# INV_H.net
KiCad netlist of a schematic drawn in EAGLE
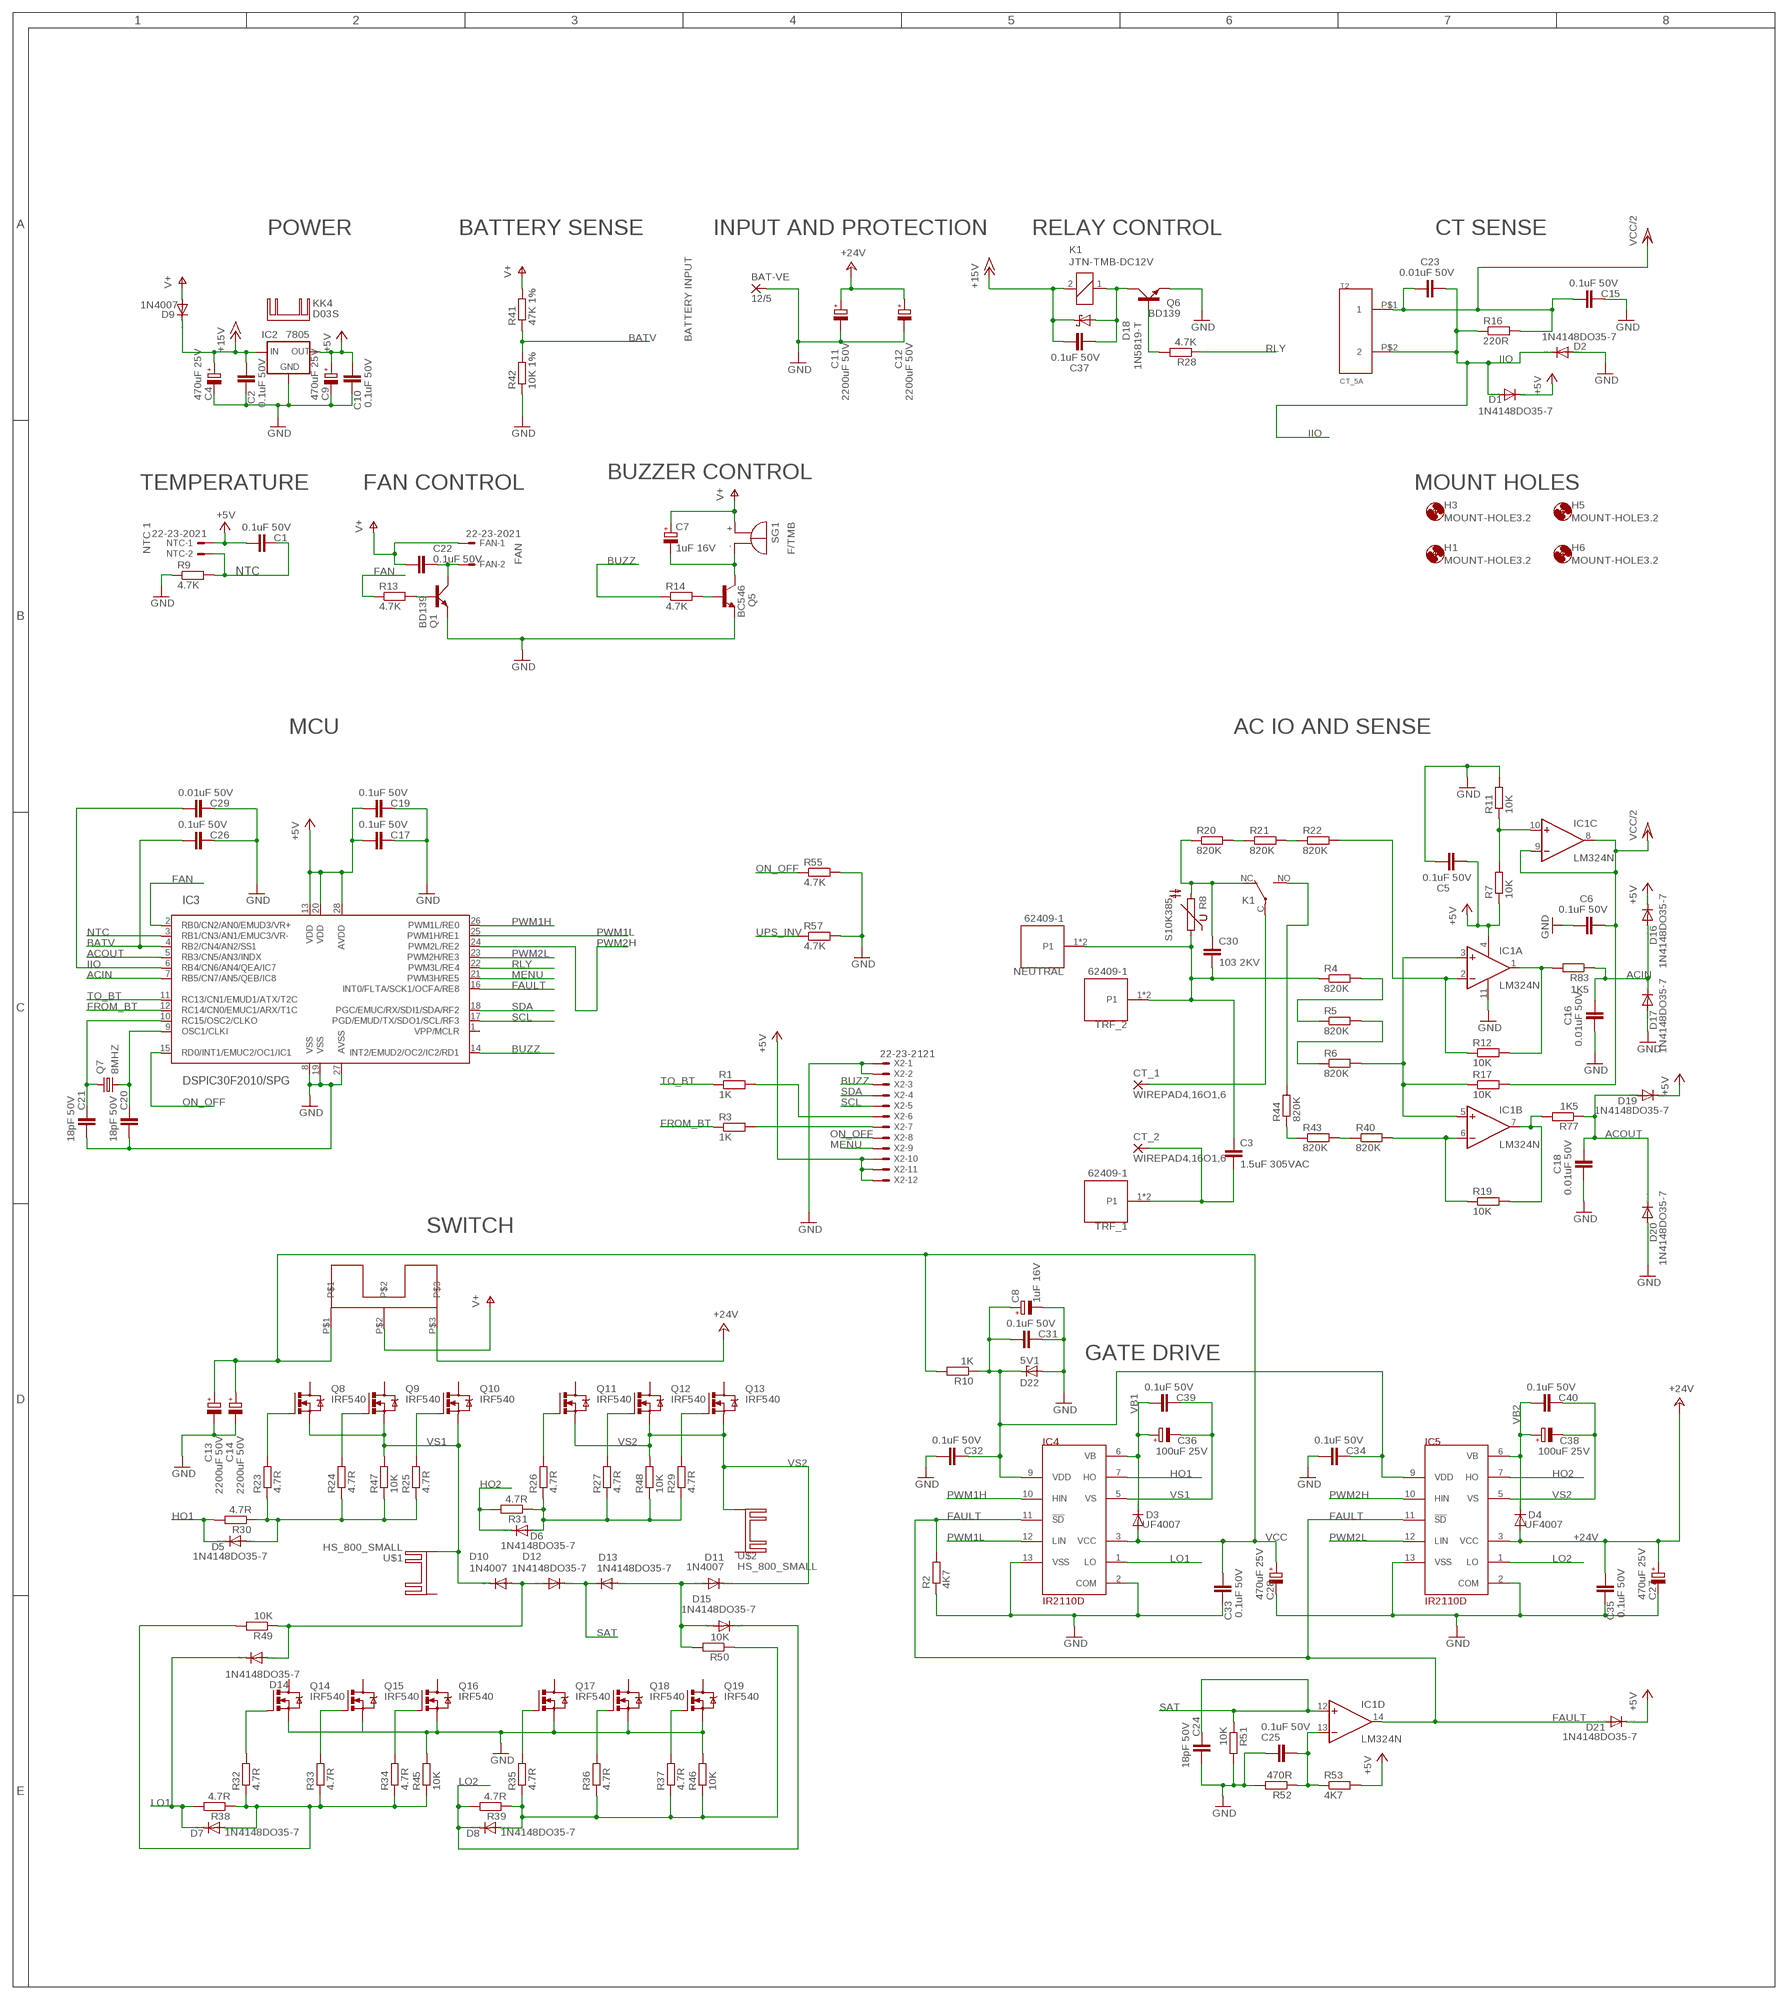
[diagram p0: schematic, sheet 1]

(export (version "E")
  (design (tool "Eeschema 10.0.6"))
  (components
    (comp (ref "BAT-VE")
      (value "12/5")
      (footprint "eagle-import:8_5")
      (libsource (lib "eagle-import") (part "12/5"))
    )
    (comp (ref "C1")
      (value "0.1uF 50V")
      (footprint "eagle-import:C025-025X050")
      (libsource (lib "eagle-import") (part "C-EU025-025X050"))
    )
    (comp (ref "C2")
      (value "0.1uF 50V")
      (footprint "eagle-import:C025-025X050")
      (libsource (lib "eagle-import") (part "C-EU025-025X050"))
    )
    (comp (ref "C3")
      (value "1.5uF 305VAC")
      (footprint "eagle-import:C275-113X316")
      (libsource (lib "eagle-import") (part "C-EU275-113X316"))
    )
    (comp (ref "C4")
      (value "470uF 25V")
      (footprint "eagle-import:E3,5-8")
      (libsource (lib "eagle-import") (part "CPOL-EUE3.5-8"))
    )
    (comp (ref "C5")
      (value "0.1uF 50V")
      (footprint "eagle-import:C025-025X050")
      (libsource (lib "eagle-import") (part "C-EU025-025X050"))
    )
    (comp (ref "C6")
      (value "0.1uF 50V")
      (footprint "eagle-import:C025-025X050")
      (libsource (lib "eagle-import") (part "C-EU025-025X050"))
    )
    (comp (ref "C7")
      (value "1uF 16V")
      (footprint "eagle-import:E1,8-4")
      (libsource (lib "eagle-import") (part "CPOL-EUE1.8-4"))
    )
    (comp (ref "C8")
      (value "1uF 16V")
      (footprint "eagle-import:E1,8-4")
      (libsource (lib "eagle-import") (part "CPOL-EUE1.8-4"))
    )
    (comp (ref "C9")
      (value "470uF 25V")
      (footprint "eagle-import:E3,5-8")
      (libsource (lib "eagle-import") (part "CPOL-EUE3.5-8"))
    )
    (comp (ref "C10")
      (value "0.1uF 50V")
      (footprint "eagle-import:C025-025X050")
      (libsource (lib "eagle-import") (part "C-EU025-025X050"))
    )
    (comp (ref "C11")
      (value "2200uF 50V")
      (footprint "eagle-import:E7,5-16")
      (libsource (lib "eagle-import") (part "CPOL-EUE7.5-16"))
    )
    (comp (ref "C12")
      (value "2200uF 50V")
      (footprint "eagle-import:E7,5-16")
      (libsource (lib "eagle-import") (part "CPOL-EUE7.5-16"))
    )
    (comp (ref "C13")
      (value "2200uF 50V")
      (footprint "eagle-import:E7,5-16")
      (libsource (lib "eagle-import") (part "CPOL-EUE7.5-16"))
    )
    (comp (ref "C14")
      (value "2200uF 50V")
      (footprint "eagle-import:E7,5-16")
      (libsource (lib "eagle-import") (part "CPOL-EUE7.5-16"))
    )
    (comp (ref "C15")
      (value "0.1uF 50V")
      (footprint "eagle-import:C025-025X050")
      (libsource (lib "eagle-import") (part "C-EU025-025X050"))
    )
    (comp (ref "C16")
      (value "0.01uF 50V")
      (footprint "eagle-import:C025-025X050")
      (libsource (lib "eagle-import") (part "C-EU025-025X050"))
    )
    (comp (ref "C17")
      (value "0.1uF 50V")
      (footprint "eagle-import:C025-025X050")
      (libsource (lib "eagle-import") (part "C-EU025-025X050"))
    )
    (comp (ref "C18")
      (value "0.01uF 50V")
      (footprint "eagle-import:C025-025X050")
      (libsource (lib "eagle-import") (part "C-EU025-025X050"))
    )
    (comp (ref "C19")
      (value "0.1uF 50V")
      (footprint "eagle-import:C025-025X050")
      (libsource (lib "eagle-import") (part "C-EU025-025X050"))
    )
    (comp (ref "C20")
      (value "18pF 50V")
      (footprint "eagle-import:C025-025X050")
      (libsource (lib "eagle-import") (part "C-EU025-025X050"))
    )
    (comp (ref "C21")
      (value "18pF 50V")
      (footprint "eagle-import:C025-025X050")
      (libsource (lib "eagle-import") (part "C-EU025-025X050"))
    )
    (comp (ref "C22")
      (value "0.1uF 50V")
      (footprint "eagle-import:C025-025X050")
      (libsource (lib "eagle-import") (part "C-EU025-025X050"))
    )
    (comp (ref "C23")
      (value "0.01uF 50V")
      (footprint "eagle-import:C025-025X050")
      (libsource (lib "eagle-import") (part "C-EU025-025X050"))
    )
    (comp (ref "C24")
      (value "18pF 50V")
      (footprint "eagle-import:C025-025X050")
      (libsource (lib "eagle-import") (part "C-EU025-025X050"))
    )
    (comp (ref "C25")
      (value "0.1uF 50V")
      (footprint "eagle-import:C025-025X050")
      (libsource (lib "eagle-import") (part "C-EU025-025X050"))
    )
    (comp (ref "C26")
      (value "0.1uF 50V")
      (footprint "eagle-import:C025-025X050")
      (libsource (lib "eagle-import") (part "C-EU025-025X050"))
    )
    (comp (ref "C27")
      (value "470uF 25V")
      (footprint "eagle-import:E3,5-8")
      (libsource (lib "eagle-import") (part "CPOL-EUE3.5-8"))
    )
    (comp (ref "C28")
      (value "470uF 25V")
      (footprint "eagle-import:E3,5-8")
      (libsource (lib "eagle-import") (part "CPOL-EUE3.5-8"))
    )
    (comp (ref "C29")
      (value "0.01uF 50V")
      (footprint "eagle-import:C025-025X050")
      (libsource (lib "eagle-import") (part "C-EU025-025X050"))
    )
    (comp (ref "C30")
      (value "103 2KV")
      (footprint "eagle-import:C075-032X103")
      (libsource (lib "eagle-import") (part "C-EU075-032X103"))
    )
    (comp (ref "C31")
      (value "0.1uF 50V")
      (footprint "eagle-import:C025-025X050")
      (libsource (lib "eagle-import") (part "C-EU025-025X050"))
    )
    (comp (ref "C32")
      (value "0.1uF 50V")
      (footprint "eagle-import:C025-025X050")
      (libsource (lib "eagle-import") (part "C-EU025-025X050"))
    )
    (comp (ref "C33")
      (value "0.1uF 50V")
      (footprint "eagle-import:C025-025X050")
      (libsource (lib "eagle-import") (part "C-EU025-025X050"))
    )
    (comp (ref "C34")
      (value "0.1uF 50V")
      (footprint "eagle-import:C025-025X050")
      (libsource (lib "eagle-import") (part "C-EU025-025X050"))
    )
    (comp (ref "C35")
      (value "0.1uF 50V")
      (footprint "eagle-import:C025-025X050")
      (libsource (lib "eagle-import") (part "C-EU025-025X050"))
    )
    (comp (ref "C36")
      (value "100uF 25V")
      (footprint "eagle-import:E2,5-6")
      (libsource (lib "eagle-import") (part "CPOL-EUE2.5-6"))
    )
    (comp (ref "C37")
      (value "0.1uF 50V")
      (footprint "eagle-import:C025-025X050")
      (libsource (lib "eagle-import") (part "C-EU025-025X050"))
    )
    (comp (ref "C38")
      (value "100uF 25V")
      (footprint "eagle-import:E2,5-6")
      (libsource (lib "eagle-import") (part "CPOL-EUE2.5-6"))
    )
    (comp (ref "C39")
      (value "0.1uF 50V")
      (footprint "eagle-import:C025-025X050")
      (libsource (lib "eagle-import") (part "C-EU025-025X050"))
    )
    (comp (ref "C40")
      (value "0.1uF 50V")
      (footprint "eagle-import:C025-025X050")
      (libsource (lib "eagle-import") (part "C-EU025-025X050"))
    )
    (comp (ref "CT_1")
      (value "WIREPAD4,16O1,6")
      (footprint "eagle-import:4,16O1,6")
      (libsource (lib "eagle-import") (part "WIREPAD4,16O1,6"))
    )
    (comp (ref "CT_2")
      (value "WIREPAD4,16O1,6")
      (footprint "eagle-import:4,16O1,6")
      (libsource (lib "eagle-import") (part "WIREPAD4,16O1,6"))
    )
    (comp (ref "D1")
      (value "1N4148DO35-7")
      (footprint "eagle-import:DO35-7")
      (libsource (lib "eagle-import") (part "1N4148DO35-7"))
    )
    (comp (ref "D2")
      (value "1N4148DO35-7")
      (footprint "eagle-import:DO35-7")
      (libsource (lib "eagle-import") (part "1N4148DO35-7"))
    )
    (comp (ref "D3")
      (value "UF4007")
      (footprint "eagle-import:DO41-10")
      (libsource (lib "eagle-import") (part "1N4004"))
    )
    (comp (ref "D4")
      (value "UF4007")
      (footprint "eagle-import:DO41-10")
      (libsource (lib "eagle-import") (part "1N4004"))
    )
    (comp (ref "D5")
      (value "1N4148DO35-7")
      (footprint "eagle-import:DO35-7")
      (libsource (lib "eagle-import") (part "1N4148DO35-7"))
    )
    (comp (ref "D6")
      (value "1N4148DO35-7")
      (footprint "eagle-import:DO35-7")
      (libsource (lib "eagle-import") (part "1N4148DO35-7"))
    )
    (comp (ref "D7")
      (value "1N4148DO35-7")
      (footprint "eagle-import:DO35-7")
      (libsource (lib "eagle-import") (part "1N4148DO35-7"))
    )
    (comp (ref "D8")
      (value "1N4148DO35-7")
      (footprint "eagle-import:DO35-7")
      (libsource (lib "eagle-import") (part "1N4148DO35-7"))
    )
    (comp (ref "D9")
      (value "1N4007")
      (footprint "eagle-import:DO41-10")
      (libsource (lib "eagle-import") (part "1N4004"))
    )
    (comp (ref "D10")
      (value "1N4007")
      (footprint "eagle-import:DO41-10")
      (libsource (lib "eagle-import") (part "1N4004"))
    )
    (comp (ref "D11")
      (value "1N4007")
      (footprint "eagle-import:DO41-10")
      (libsource (lib "eagle-import") (part "1N4004"))
    )
    (comp (ref "D12")
      (value "1N4148DO35-7")
      (footprint "eagle-import:DO35-7")
      (libsource (lib "eagle-import") (part "1N4148DO35-7"))
    )
    (comp (ref "D13")
      (value "1N4148DO35-7")
      (footprint "eagle-import:DO35-7")
      (libsource (lib "eagle-import") (part "1N4148DO35-7"))
    )
    (comp (ref "D14")
      (value "1N4148DO35-7")
      (footprint "eagle-import:DO35-7")
      (libsource (lib "eagle-import") (part "1N4148DO35-7"))
    )
    (comp (ref "D15")
      (value "1N4148DO35-7")
      (footprint "eagle-import:DO35-7")
      (libsource (lib "eagle-import") (part "1N4148DO35-7"))
    )
    (comp (ref "D16")
      (value "1N4148DO35-7")
      (footprint "eagle-import:DO35-7")
      (libsource (lib "eagle-import") (part "1N4148DO35-7"))
    )
    (comp (ref "D17")
      (value "1N4148DO35-7")
      (footprint "eagle-import:DO35-7")
      (libsource (lib "eagle-import") (part "1N4148DO35-7"))
    )
    (comp (ref "D18")
      (value "1N5819-T")
      (footprint "eagle-import:DO41-7.6")
      (libsource (lib "eagle-import") (part "1N5819-T"))
    )
    (comp (ref "D19")
      (value "1N4148DO35-7")
      (footprint "eagle-import:DO35-7")
      (libsource (lib "eagle-import") (part "1N4148DO35-7"))
    )
    (comp (ref "D20")
      (value "1N4148DO35-7")
      (footprint "eagle-import:DO35-7")
      (libsource (lib "eagle-import") (part "1N4148DO35-7"))
    )
    (comp (ref "D21")
      (value "1N4148DO35-7")
      (footprint "eagle-import:DO35-7")
      (libsource (lib "eagle-import") (part "1N4148DO35-7"))
    )
    (comp (ref "D22")
      (value "5V1")
      (footprint "eagle-import:DO34Z7")
      (libsource (lib "eagle-import") (part "ZENER-DIODEDO34-7"))
    )
    (comp (ref "FAN")
      (value "22-23-2021")
      (footprint "eagle-import:22-23-2021")
      (fields (field (name "MF") "MOLEX"))
      (libsource (lib "eagle-import") (part "22-23-2021"))
    )
    (comp (ref "H1")
      (value "MOUNT-HOLE3.2")
      (footprint "eagle-import:3,2")
      (libsource (lib "eagle-import") (part "MOUNT-HOLE3.2"))
    )
    (comp (ref "H3")
      (value "MOUNT-HOLE3.2")
      (footprint "eagle-import:3,2")
      (libsource (lib "eagle-import") (part "MOUNT-HOLE3.2"))
    )
    (comp (ref "H5")
      (value "MOUNT-HOLE3.2")
      (footprint "eagle-import:3,2")
      (libsource (lib "eagle-import") (part "MOUNT-HOLE3.2"))
    )
    (comp (ref "H6")
      (value "MOUNT-HOLE3.2")
      (footprint "eagle-import:3,2")
      (libsource (lib "eagle-import") (part "MOUNT-HOLE3.2"))
    )
    (comp (ref "IC1")
      (value "LM324N")
      (footprint "eagle-import:DIL14")
      (libsource (lib "eagle-import") (part "LM324N"))
    )
    (comp (ref "IC2")
      (value "7805")
      (footprint "eagle-import:78XXS")
      (libsource (lib "eagle-import") (part "78XXS"))
    )
    (comp (ref "IC3")
      (value "DSPIC30F2010/SPG")
      (footprint "eagle-import:DIL28-3")
      (libsource (lib "eagle-import") (part "DSPIC30F2010/SPG"))
    )
    (comp (ref "IC4")
      (value "IR2110D")
      (footprint "eagle-import:DIL14")
      (libsource (lib "eagle-import") (part "IR2110D"))
    )
    (comp (ref "IC5")
      (value "IR2110D")
      (footprint "eagle-import:DIL14")
      (libsource (lib "eagle-import") (part "IR2110D"))
    )
    (comp (ref "K1")
      (value "JTN-TMB-DC12V")
      (footprint "eagle-import:JT-TMB")
      (libsource (lib "eagle-import") (part "JT?-N-TMBDC12V"))
    )
    (comp (ref "KK4")
      (value "D03S")
      (footprint "eagle-import:D03S")
      (libsource (lib "eagle-import") (part "D03S"))
    )
    (comp (ref "KK5")
      (value "HS_800_BIG")
      (footprint "eagle-import:800W_BIG")
      (libsource (lib "eagle-import") (part "HS_800_BIG"))
    )
    (comp (ref "NEUTRAL")
      (value "62409-1")
      (footprint "eagle-import:TE_62409-1")
      (fields (field (name "MF") "TE Connectivity"))
      (libsource (lib "eagle-import") (part "62409-1"))
    )
    (comp (ref "NTC")
      (value "22-23-2021")
      (footprint "eagle-import:22-23-2021")
      (fields (field (name "MF") "MOLEX"))
      (libsource (lib "eagle-import") (part "22-23-2021"))
    )
    (comp (ref "Q1")
      (value "BD139")
      (footprint "eagle-import:TO126AV")
      (libsource (lib "eagle-import") (part "BD139"))
    )
    (comp (ref "Q5")
      (value "BC546")
      (footprint "eagle-import:TO92-EBC")
      (libsource (lib "eagle-import") (part "BC548"))
    )
    (comp (ref "Q6")
      (value "BD139")
      (footprint "eagle-import:TO126AV")
      (libsource (lib "eagle-import") (part "BD139"))
    )
    (comp (ref "Q7")
      (value "8MHZ")
      (footprint "eagle-import:HC49_S")
      (libsource (lib "eagle-import") (part "CRYSTALHC49S"))
    )
    (comp (ref "Q8")
      (value "IRF540")
      (footprint "eagle-import:TO220BV")
      (libsource (lib "eagle-import") (part "IRF540"))
    )
    (comp (ref "Q9")
      (value "IRF540")
      (footprint "eagle-import:TO220BV")
      (libsource (lib "eagle-import") (part "IRF540"))
    )
    (comp (ref "Q10")
      (value "IRF540")
      (footprint "eagle-import:TO220BV")
      (libsource (lib "eagle-import") (part "IRF540"))
    )
    (comp (ref "Q11")
      (value "IRF540")
      (footprint "eagle-import:TO220BV")
      (libsource (lib "eagle-import") (part "IRF540"))
    )
    (comp (ref "Q12")
      (value "IRF540")
      (footprint "eagle-import:TO220BV")
      (libsource (lib "eagle-import") (part "IRF540"))
    )
    (comp (ref "Q13")
      (value "IRF540")
      (footprint "eagle-import:TO220BV")
      (libsource (lib "eagle-import") (part "IRF540"))
    )
    (comp (ref "Q14")
      (value "IRF540")
      (footprint "eagle-import:TO220BV")
      (libsource (lib "eagle-import") (part "IRF540"))
    )
    (comp (ref "Q15")
      (value "IRF540")
      (footprint "eagle-import:TO220BV")
      (libsource (lib "eagle-import") (part "IRF540"))
    )
    (comp (ref "Q16")
      (value "IRF540")
      (footprint "eagle-import:TO220BV")
      (libsource (lib "eagle-import") (part "IRF540"))
    )
    (comp (ref "Q17")
      (value "IRF540")
      (footprint "eagle-import:TO220BV")
      (libsource (lib "eagle-import") (part "IRF540"))
    )
    (comp (ref "Q18")
      (value "IRF540")
      (footprint "eagle-import:TO220BV")
      (libsource (lib "eagle-import") (part "IRF540"))
    )
    (comp (ref "Q19")
      (value "IRF540")
      (footprint "eagle-import:TO220BV")
      (libsource (lib "eagle-import") (part "IRF540"))
    )
    (comp (ref "R1")
      (value "1K")
      (footprint "eagle-import:0204_7")
      (libsource (lib "eagle-import") (part "R-EU_0204/7"))
    )
    (comp (ref "R2")
      (value "4K7")
      (footprint "eagle-import:0204_7")
      (libsource (lib "eagle-import") (part "R-EU_0204/7"))
    )
    (comp (ref "R3")
      (value "1K")
      (footprint "eagle-import:0204_7")
      (libsource (lib "eagle-import") (part "R-EU_0204/7"))
    )
    (comp (ref "R4")
      (value "820K")
      (footprint "eagle-import:0204_7")
      (libsource (lib "eagle-import") (part "R-EU_0204/7"))
    )
    (comp (ref "R5")
      (value "820K")
      (footprint "eagle-import:0204_7")
      (libsource (lib "eagle-import") (part "R-EU_0204/7"))
    )
    (comp (ref "R6")
      (value "820K")
      (footprint "eagle-import:0204_7")
      (libsource (lib "eagle-import") (part "R-EU_0204/7"))
    )
    (comp (ref "R7")
      (value "10K")
      (footprint "eagle-import:0204_7")
      (libsource (lib "eagle-import") (part "R-EU_0204/7"))
    )
    (comp (ref "R8")
      (value "S10K385")
      (footprint "eagle-import:S10K385")
      (libsource (lib "eagle-import") (part "S10K385"))
    )
    (comp (ref "R9")
      (value "4.7K")
      (footprint "eagle-import:0204_7")
      (libsource (lib "eagle-import") (part "R-EU_0204/7"))
    )
    (comp (ref "R10")
      (value "1K")
      (footprint "eagle-import:0204_7")
      (libsource (lib "eagle-import") (part "R-EU_0204/7"))
    )
    (comp (ref "R11")
      (value "10K")
      (footprint "eagle-import:0204_7")
      (libsource (lib "eagle-import") (part "R-EU_0204/7"))
    )
    (comp (ref "R12")
      (value "10K")
      (footprint "eagle-import:0204_7")
      (libsource (lib "eagle-import") (part "R-EU_0204/7"))
    )
    (comp (ref "R13")
      (value "4.7K")
      (footprint "eagle-import:0204_7")
      (libsource (lib "eagle-import") (part "R-EU_0204/7"))
    )
    (comp (ref "R14")
      (value "4.7K")
      (footprint "eagle-import:0204_7")
      (libsource (lib "eagle-import") (part "R-EU_0204/7"))
    )
    (comp (ref "R16")
      (value "220R")
      (footprint "eagle-import:0204_7")
      (libsource (lib "eagle-import") (part "R-EU_0204/7"))
    )
    (comp (ref "R17")
      (value "10K")
      (footprint "eagle-import:0204_7")
      (libsource (lib "eagle-import") (part "R-EU_0204/7"))
    )
    (comp (ref "R19")
      (value "10K")
      (footprint "eagle-import:0204_7")
      (libsource (lib "eagle-import") (part "R-EU_0204/7"))
    )
    (comp (ref "R20")
      (value "820K")
      (footprint "eagle-import:0204_7")
      (libsource (lib "eagle-import") (part "R-EU_0204/7"))
    )
    (comp (ref "R21")
      (value "820K")
      (footprint "eagle-import:0204_7")
      (libsource (lib "eagle-import") (part "R-EU_0204/7"))
    )
    (comp (ref "R22")
      (value "820K")
      (footprint "eagle-import:0204_7")
      (libsource (lib "eagle-import") (part "R-EU_0204/7"))
    )
    (comp (ref "R23")
      (value "4.7R")
      (footprint "eagle-import:0204_7")
      (libsource (lib "eagle-import") (part "R-EU_0204/7"))
    )
    (comp (ref "R24")
      (value "4.7R")
      (footprint "eagle-import:0204_7")
      (libsource (lib "eagle-import") (part "R-EU_0204/7"))
    )
    (comp (ref "R25")
      (value "4.7R")
      (footprint "eagle-import:0204_7")
      (libsource (lib "eagle-import") (part "R-EU_0204/7"))
    )
    (comp (ref "R26")
      (value "4.7R")
      (footprint "eagle-import:0204_7")
      (libsource (lib "eagle-import") (part "R-EU_0204/7"))
    )
    (comp (ref "R27")
      (value "4.7R")
      (footprint "eagle-import:0204_7")
      (libsource (lib "eagle-import") (part "R-EU_0204/7"))
    )
    (comp (ref "R28")
      (value "4.7K")
      (footprint "eagle-import:0204_7")
      (libsource (lib "eagle-import") (part "R-EU_0204/7"))
    )
    (comp (ref "R29")
      (value "4.7R")
      (footprint "eagle-import:0204_7")
      (libsource (lib "eagle-import") (part "R-EU_0204/7"))
    )
    (comp (ref "R30")
      (value "4.7R")
      (footprint "eagle-import:0204_7")
      (libsource (lib "eagle-import") (part "R-EU_0204/7"))
    )
    (comp (ref "R31")
      (value "4.7R")
      (footprint "eagle-import:0204_7")
      (libsource (lib "eagle-import") (part "R-EU_0204/7"))
    )
    (comp (ref "R32")
      (value "4.7R")
      (footprint "eagle-import:0204_7")
      (libsource (lib "eagle-import") (part "R-EU_0204/7"))
    )
    (comp (ref "R33")
      (value "4.7R")
      (footprint "eagle-import:0204_7")
      (libsource (lib "eagle-import") (part "R-EU_0204/7"))
    )
    (comp (ref "R34")
      (value "4.7R")
      (footprint "eagle-import:0204_7")
      (libsource (lib "eagle-import") (part "R-EU_0204/7"))
    )
    (comp (ref "R35")
      (value "4.7R")
      (footprint "eagle-import:0204_7")
      (libsource (lib "eagle-import") (part "R-EU_0204/7"))
    )
    (comp (ref "R36")
      (value "4.7R")
      (footprint "eagle-import:0204_7")
      (libsource (lib "eagle-import") (part "R-EU_0204/7"))
    )
    (comp (ref "R37")
      (value "4.7R")
      (footprint "eagle-import:0204_7")
      (libsource (lib "eagle-import") (part "R-EU_0204/7"))
    )
    (comp (ref "R38")
      (value "4.7R")
      (footprint "eagle-import:0204_7")
      (libsource (lib "eagle-import") (part "R-EU_0204/7"))
    )
    (comp (ref "R39")
      (value "4.7R")
      (footprint "eagle-import:0204_7")
      (libsource (lib "eagle-import") (part "R-EU_0204/7"))
    )
    (comp (ref "R40")
      (value "820K")
      (footprint "eagle-import:0204_7")
      (libsource (lib "eagle-import") (part "R-EU_0204/7"))
    )
    (comp (ref "R41")
      (value "47K 1%")
      (footprint "eagle-import:0204_7")
      (libsource (lib "eagle-import") (part "R-EU_0204/7"))
    )
    (comp (ref "R42")
      (value "10K 1%")
      (footprint "eagle-import:0204_7")
      (libsource (lib "eagle-import") (part "R-EU_0204/7"))
    )
    (comp (ref "R43")
      (value "820K")
      (footprint "eagle-import:0204_7")
      (libsource (lib "eagle-import") (part "R-EU_0204/7"))
    )
    (comp (ref "R44")
      (value "820K")
      (footprint "eagle-import:0204_7")
      (libsource (lib "eagle-import") (part "R-EU_0204/7"))
    )
    (comp (ref "R45")
      (value "10K")
      (footprint "eagle-import:0204_7")
      (libsource (lib "eagle-import") (part "R-EU_0204/7"))
    )
    (comp (ref "R46")
      (value "10K")
      (footprint "eagle-import:0204_7")
      (libsource (lib "eagle-import") (part "R-EU_0204/7"))
    )
    (comp (ref "R47")
      (value "10K")
      (footprint "eagle-import:0204_7")
      (libsource (lib "eagle-import") (part "R-EU_0204/7"))
    )
    (comp (ref "R48")
      (value "10K")
      (footprint "eagle-import:0204_7")
      (libsource (lib "eagle-import") (part "R-EU_0204/7"))
    )
    (comp (ref "R49")
      (value "10K")
      (footprint "eagle-import:0204_7")
      (libsource (lib "eagle-import") (part "R-EU_0204/7"))
    )
    (comp (ref "R50")
      (value "10K")
      (footprint "eagle-import:0204_7")
      (libsource (lib "eagle-import") (part "R-EU_0204/7"))
    )
    (comp (ref "R51")
      (value "10K")
      (footprint "eagle-import:0204_7")
      (libsource (lib "eagle-import") (part "R-EU_0204/7"))
    )
    (comp (ref "R52")
      (value "470R")
      (footprint "eagle-import:0204_7")
      (libsource (lib "eagle-import") (part "R-EU_0204/7"))
    )
    (comp (ref "R53")
      (value "4K7")
      (footprint "eagle-import:0204_7")
      (libsource (lib "eagle-import") (part "R-EU_0204/7"))
    )
    (comp (ref "R55")
      (value "4.7K")
      (footprint "eagle-import:0204_7")
      (libsource (lib "eagle-import") (part "R-EU_0204/7"))
    )
    (comp (ref "R57")
      (value "4.7K")
      (footprint "eagle-import:0204_7")
      (libsource (lib "eagle-import") (part "R-EU_0204/7"))
    )
    (comp (ref "R77")
      (value "1K5")
      (footprint "eagle-import:0204_7")
      (libsource (lib "eagle-import") (part "R-EU_0204/7"))
    )
    (comp (ref "R83")
      (value "1K5")
      (footprint "eagle-import:0204_7")
      (libsource (lib "eagle-import") (part "R-EU_0204/7"))
    )
    (comp (ref "SG1")
      (value "F/TMB")
      (footprint "eagle-import:F_TMB")
      (libsource (lib "eagle-import") (part "F/TMB"))
    )
    (comp (ref "T2")
      (value "CT_5A")
      (footprint "eagle-import:CT_5A")
      (libsource (lib "eagle-import") (part "CT_5A"))
    )
    (comp (ref "TRF_1")
      (value "62409-1")
      (footprint "eagle-import:TE_62409-1")
      (fields (field (name "MF") "TE Connectivity"))
      (libsource (lib "eagle-import") (part "62409-1"))
    )
    (comp (ref "TRF_2")
      (value "62409-1")
      (footprint "eagle-import:TE_62409-1")
      (fields (field (name "MF") "TE Connectivity"))
      (libsource (lib "eagle-import") (part "62409-1"))
    )
    (comp (ref "U$1")
      (value "HS_800_SMALL")
      (footprint "eagle-import:800W_SMALL")
      (libsource (lib "eagle-import") (part "HS_800_SMALL"))
    )
    (comp (ref "U$2")
      (value "HS_800_SMALL")
      (footprint "eagle-import:800W_SMALL")
      (libsource (lib "eagle-import") (part "HS_800_SMALL"))
    )
    (comp (ref "X2")
      (value "22-23-2121")
      (footprint "eagle-import:22-23-2121")
      (fields (field (name "MF") "MOLEX"))
      (libsource (lib "eagle-import") (part "22-23-2121"))
    )
  )
  (nets
    (net (code "1") (name "+5V") (class "Default")
      (node (ref "C1") (pin "2") (pinfunction "2_2") (pintype "passive"))
      (node (ref "C10") (pin "2") (pinfunction "2_2") (pintype "passive"))
      (node (ref "C17") (pin "2") (pinfunction "2_2") (pintype "passive"))
      (node (ref "C19") (pin "2") (pinfunction "2_2") (pintype "passive"))
      (node (ref "C5") (pin "2") (pinfunction "2_2") (pintype "passive"))
      (node (ref "C9") (pin "+") (pinfunction "+_+") (pintype "passive"))
      (node (ref "D1") (pin "C") (pinfunction "C_C") (pintype "passive"))
      (node (ref "D16") (pin "C") (pinfunction "C_C") (pintype "passive"))
      (node (ref "D19") (pin "C") (pinfunction "C_C") (pintype "passive"))
      (node (ref "D21") (pin "C") (pinfunction "C_C") (pintype "passive"))
      (node (ref "IC1") (pin "4") (pinfunction "V+_4") (pintype "power_in"))
      (node (ref "IC2") (pin "OUT") (pinfunction "OUT_OUT") (pintype "passive"))
      (node (ref "IC3") (pin "13") (pinfunction "VDD_13") (pintype "power_in"))
      (node (ref "IC3") (pin "20") (pinfunction "VDD_20") (pintype "power_in"))
      (node (ref "IC3") (pin "28") (pinfunction "AVDD_28") (pintype "power_in"))
      (node (ref "NTC") (pin "1") (pinfunction "S_1") (pintype "passive"))
      (node (ref "R53") (pin "4") (pinfunction "2_4") (pintype "passive"))
      (node (ref "R7") (pin "3") (pinfunction "1_3") (pintype "passive"))
      (node (ref "X2") (pin "10") (pinfunction "S_10") (pintype "passive"))
      (node (ref "X2") (pin "11") (pinfunction "S_11") (pintype "passive"))
      (node (ref "X2") (pin "12") (pinfunction "S_12") (pintype "passive"))
    )
    (net (code "2") (name "+15V") (class "Default")
      (node (ref "C2") (pin "2") (pinfunction "2_2") (pintype "passive"))
      (node (ref "C37") (pin "1") (pinfunction "1_1") (pintype "passive"))
      (node (ref "C4") (pin "+") (pinfunction "+_+") (pintype "passive"))
      (node (ref "D18") (pin "C") (pinfunction "C_C") (pintype "passive"))
      (node (ref "D9") (pin "C") (pinfunction "C_C") (pintype "passive"))
      (node (ref "IC2") (pin "IN") (pinfunction "IN_IN") (pintype "input"))
      (node (ref "K1") (pin "2") (pinfunction "2_2") (pintype "passive"))
    )
    (net (code "3") (name "+24V") (class "Default")
      (node (ref "C11") (pin "+") (pinfunction "+_+") (pintype "passive"))
      (node (ref "C12") (pin "+") (pinfunction "+_+") (pintype "passive"))
      (node (ref "C27") (pin "+") (pinfunction "+_+") (pintype "passive"))
      (node (ref "C35") (pin "2") (pinfunction "2_2") (pintype "passive"))
      (node (ref "D4") (pin "A") (pinfunction "A_A") (pintype "passive"))
      (node (ref "IC5") (pin "3") (pinfunction "VCC_3") (pintype "power_in"))
      (node (ref "KK5") (pin "P$3") (pinfunction "P$3_P$3") (pintype "bidirectional"))
    )
    (net (code "4") (name "/ACIN") (class "Default")
      (node (ref "C16") (pin "1") (pinfunction "1_1") (pintype "passive"))
      (node (ref "D16") (pin "A") (pinfunction "A_A") (pintype "passive"))
      (node (ref "D17") (pin "C") (pinfunction "C_C") (pintype "passive"))
      (node (ref "IC3") (pin "7") (pinfunction "RB5/CN7/AN5/QEB/IC8_7") (pintype "bidirectional"))
      (node (ref "R83") (pin "3") (pinfunction "1_3") (pintype "passive"))
    )
    (net (code "5") (name "/ACOUT") (class "Default")
      (node (ref "C18") (pin "1") (pinfunction "1_1") (pintype "passive"))
      (node (ref "D19") (pin "A") (pinfunction "A_A") (pintype "passive"))
      (node (ref "D20") (pin "C") (pinfunction "C_C") (pintype "passive"))
      (node (ref "IC3") (pin "5") (pinfunction "RB3/CN5/AN3/INDX_5") (pintype "bidirectional"))
      (node (ref "R77") (pin "3") (pinfunction "1_3") (pintype "passive"))
    )
    (net (code "6") (name "/BATV") (class "Default")
      (node (ref "C26") (pin "2") (pinfunction "2_2") (pintype "passive"))
      (node (ref "IC3") (pin "4") (pinfunction "RB2/CN4/AN2/SS1_4") (pintype "bidirectional"))
      (node (ref "R41") (pin "3") (pinfunction "1_3") (pintype "passive"))
      (node (ref "R42") (pin "4") (pinfunction "2_4") (pintype "passive"))
    )
    (net (code "7") (name "/BUZZ") (class "Default")
      (node (ref "IC3") (pin "14") (pinfunction "INT2/EMUD2/OC2/IC2/RD1_14") (pintype "bidirectional"))
      (node (ref "R14") (pin "3") (pinfunction "1_3") (pintype "passive"))
      (node (ref "X2") (pin "3") (pinfunction "S_3") (pintype "passive"))
    )
    (net (code "8") (name "/FAN") (class "Default")
      (node (ref "IC3") (pin "2") (pinfunction "RB0/CN2/AN0/EMUD3/VR+_2") (pintype "bidirectional"))
      (node (ref "R13") (pin "3") (pinfunction "1_3") (pintype "passive"))
    )
    (net (code "9") (name "/FAULT") (class "Default")
      (node (ref "D21") (pin "A") (pinfunction "A_A") (pintype "passive"))
      (node (ref "IC1") (pin "14") (pinfunction "OUT_14") (pintype "output"))
      (node (ref "IC3") (pin "16") (pinfunction "INT0/FLTA/SCK1/OCFA/RE8_16") (pintype "bidirectional"))
      (node (ref "IC4") (pin "11") (pinfunction "~{SD}_11") (pintype "input"))
      (node (ref "IC5") (pin "11") (pinfunction "~{SD}_11") (pintype "input"))
      (node (ref "R2") (pin "4") (pinfunction "2_4") (pintype "passive"))
    )
    (net (code "10") (name "/FROM_BT") (class "Default")
      (node (ref "IC3") (pin "12") (pinfunction "RC14/CN0/EMUC1/ARX/T1C_12") (pintype "bidirectional"))
      (node (ref "R3") (pin "3") (pinfunction "1_3") (pintype "passive"))
    )
    (net (code "11") (name "/HO1") (class "Default")
      (node (ref "D5") (pin "C") (pinfunction "C_C") (pintype "passive"))
      (node (ref "IC4") (pin "7") (pinfunction "HO_7") (pintype "output"))
      (node (ref "R30") (pin "4") (pinfunction "2_4") (pintype "passive"))
    )
    (net (code "12") (name "/HO2") (class "Default")
      (node (ref "D6") (pin "C") (pinfunction "C_C") (pintype "passive"))
      (node (ref "IC5") (pin "7") (pinfunction "HO_7") (pintype "output"))
      (node (ref "R31") (pin "4") (pinfunction "2_4") (pintype "passive"))
    )
    (net (code "13") (name "/IIO") (class "Default")
      (node (ref "C23") (pin "1") (pinfunction "1_1") (pintype "passive"))
      (node (ref "C29") (pin "2") (pinfunction "2_2") (pintype "passive"))
      (node (ref "D1") (pin "A") (pinfunction "A_A") (pintype "passive"))
      (node (ref "D2") (pin "C") (pinfunction "C_C") (pintype "passive"))
      (node (ref "IC3") (pin "6") (pinfunction "RB4/CN6/AN4/QEA/IC7_6") (pintype "bidirectional"))
      (node (ref "R16") (pin "3") (pinfunction "1_3") (pintype "passive"))
      (node (ref "T2") (pin "P$2") (pinfunction "2_P$2") (pintype "bidirectional"))
    )
    (net (code "14") (name "/LO1") (class "Default")
      (node (ref "D14") (pin "C") (pinfunction "C_C") (pintype "passive"))
      (node (ref "D7") (pin "C") (pinfunction "C_C") (pintype "passive"))
      (node (ref "IC4") (pin "1") (pinfunction "LO_1") (pintype "output"))
      (node (ref "R38") (pin "4") (pinfunction "2_4") (pintype "passive"))
    )
    (net (code "15") (name "/LO2") (class "Default")
      (node (ref "D15") (pin "C") (pinfunction "C_C") (pintype "passive"))
      (node (ref "D8") (pin "C") (pinfunction "C_C") (pintype "passive"))
      (node (ref "IC5") (pin "1") (pinfunction "LO_1") (pintype "output"))
      (node (ref "R39") (pin "4") (pinfunction "2_4") (pintype "passive"))
    )
    (net (code "16") (name "/MENU") (class "Default")
      (node (ref "IC3") (pin "21") (pinfunction "PWM3H/RE5_21") (pintype "bidirectional"))
      (node (ref "X2") (pin "9") (pinfunction "S_9") (pintype "passive"))
    )
    (net (code "17") (name "/NTC") (class "Default")
      (node (ref "C1") (pin "1") (pinfunction "1_1") (pintype "passive"))
      (node (ref "IC3") (pin "3") (pinfunction "RB1/CN3/AN1/EMUC3/VR-_3") (pintype "bidirectional"))
      (node (ref "NTC") (pin "2") (pinfunction "S_2") (pintype "passive"))
      (node (ref "R9") (pin "4") (pinfunction "2_4") (pintype "passive"))
    )
    (net (code "18") (name "/ON_OFF") (class "Default")
      (node (ref "IC3") (pin "15") (pinfunction "RD0/INT1/EMUC2/OC1/IC1_15") (pintype "bidirectional"))
      (node (ref "R55") (pin "3") (pinfunction "1_3") (pintype "passive"))
      (node (ref "X2") (pin "8") (pinfunction "S_8") (pintype "passive"))
    )
    (net (code "19") (name "/PWM1H") (class "Default")
      (node (ref "IC3") (pin "26") (pinfunction "PWM1L/RE0_26") (pintype "bidirectional"))
      (node (ref "IC4") (pin "10") (pinfunction "HIN_10") (pintype "input"))
    )
    (net (code "20") (name "/PWM1L") (class "Default")
      (node (ref "IC3") (pin "25") (pinfunction "PWM1H/RE1_25") (pintype "bidirectional"))
      (node (ref "IC4") (pin "12") (pinfunction "LIN_12") (pintype "input"))
    )
    (net (code "21") (name "/PWM2H") (class "Default")
      (node (ref "IC3") (pin "24") (pinfunction "PWM2L/RE2_24") (pintype "bidirectional"))
      (node (ref "IC5") (pin "10") (pinfunction "HIN_10") (pintype "input"))
    )
    (net (code "22") (name "/PWM2L") (class "Default")
      (node (ref "IC3") (pin "23") (pinfunction "PWM2H/RE3_23") (pintype "bidirectional"))
      (node (ref "IC5") (pin "12") (pinfunction "LIN_12") (pintype "input"))
    )
    (net (code "23") (name "/RLY") (class "Default")
      (node (ref "IC3") (pin "22") (pinfunction "PWM3L/RE4_22") (pintype "bidirectional"))
      (node (ref "R28") (pin "3") (pinfunction "1_3") (pintype "passive"))
    )
    (net (code "24") (name "/SAT") (class "Default")
      (node (ref "C24") (pin "1") (pinfunction "1_1") (pintype "passive"))
      (node (ref "D12") (pin "C") (pinfunction "C_C") (pintype "passive"))
      (node (ref "D13") (pin "C") (pinfunction "C_C") (pintype "passive"))
      (node (ref "IC1") (pin "12") (pinfunction "+IN_12") (pintype "input"))
      (node (ref "R51") (pin "3") (pinfunction "1_3") (pintype "passive"))
    )
    (net (code "25") (name "/SCL") (class "Default")
      (node (ref "IC3") (pin "17") (pinfunction "PGD/EMUD/TX/SDO1/SCL/RF3_17") (pintype "bidirectional"))
      (node (ref "X2") (pin "5") (pinfunction "S_5") (pintype "passive"))
    )
    (net (code "26") (name "/SDA") (class "Default")
      (node (ref "IC3") (pin "18") (pinfunction "PGC/EMUC/RX/SDI1/SDA/RF2_18") (pintype "bidirectional"))
      (node (ref "X2") (pin "4") (pinfunction "S_4") (pintype "passive"))
    )
    (net (code "27") (name "/TO_BT") (class "Default")
      (node (ref "IC3") (pin "11") (pinfunction "RC13/CN1/EMUD1/ATX/T2C_11") (pintype "bidirectional"))
      (node (ref "R1") (pin "3") (pinfunction "1_3") (pintype "passive"))
    )
    (net (code "28") (name "/UPS_INV") (class "Default")
      (node (ref "R57") (pin "3") (pinfunction "1_3") (pintype "passive"))
    )
    (net (code "29") (name "/VB1") (class "Default")
      (node (ref "C36") (pin "+") (pinfunction "+_+") (pintype "passive"))
      (node (ref "C39") (pin "2") (pinfunction "2_2") (pintype "passive"))
      (node (ref "D3") (pin "C") (pinfunction "C_C") (pintype "passive"))
      (node (ref "IC4") (pin "6") (pinfunction "VB_6") (pintype "power_in"))
    )
    (net (code "30") (name "/VB2") (class "Default")
      (node (ref "C38") (pin "+") (pinfunction "+_+") (pintype "passive"))
      (node (ref "C40") (pin "2") (pinfunction "2_2") (pintype "passive"))
      (node (ref "D4") (pin "C") (pinfunction "C_C") (pintype "passive"))
      (node (ref "IC5") (pin "6") (pinfunction "VB_6") (pintype "power_in"))
    )
    (net (code "31") (name "/VCC") (class "Default")
      (node (ref "C13") (pin "+") (pinfunction "+_+") (pintype "passive"))
      (node (ref "C14") (pin "+") (pinfunction "+_+") (pintype "passive"))
      (node (ref "C28") (pin "+") (pinfunction "+_+") (pintype "passive"))
      (node (ref "C33") (pin "2") (pinfunction "2_2") (pintype "passive"))
      (node (ref "D3") (pin "A") (pinfunction "A_A") (pintype "passive"))
      (node (ref "IC4") (pin "3") (pinfunction "VCC_3") (pintype "power_in"))
      (node (ref "KK5") (pin "P$1") (pinfunction "P$1_P$1") (pintype "bidirectional"))
      (node (ref "R10") (pin "4") (pinfunction "2_4") (pintype "passive"))
    )
    (net (code "32") (name "/VS1") (class "Default")
      (node (ref "C36") (pin "-") (pinfunction "-_-") (pintype "passive"))
      (node (ref "C39") (pin "1") (pinfunction "1_1") (pintype "passive"))
      (node (ref "D10") (pin "C") (pinfunction "C_C") (pintype "passive"))
      (node (ref "IC4") (pin "5") (pinfunction "VS_5") (pintype "power_in"))
      (node (ref "Q10") (pin "S") (pinfunction "S_S") (pintype "passive"))
      (node (ref "Q8") (pin "S") (pinfunction "S_S") (pintype "passive"))
      (node (ref "Q9") (pin "S") (pinfunction "S_S") (pintype "passive"))
      (node (ref "R47") (pin "4") (pinfunction "2_4") (pintype "passive"))
      (node (ref "U$1") (pin "P$2") (pinfunction "K_P$2") (pintype "passive"))
    )
    (net (code "33") (name "/VS2") (class "Default")
      (node (ref "C38") (pin "-") (pinfunction "-_-") (pintype "passive"))
      (node (ref "C40") (pin "1") (pinfunction "1_1") (pintype "passive"))
      (node (ref "D11") (pin "C") (pinfunction "C_C") (pintype "passive"))
      (node (ref "IC5") (pin "5") (pinfunction "VS_5") (pintype "power_in"))
      (node (ref "Q11") (pin "S") (pinfunction "S_S") (pintype "passive"))
      (node (ref "Q12") (pin "S") (pinfunction "S_S") (pintype "passive"))
      (node (ref "Q13") (pin "S") (pinfunction "S_S") (pintype "passive"))
      (node (ref "R48") (pin "4") (pinfunction "2_4") (pintype "passive"))
      (node (ref "U$2") (pin "P$1") (pinfunction "K_P$1") (pintype "passive"))
    )
    (net (code "34") (name "GND") (class "Default")
      (node (ref "BAT-VE") (pin "P$1") (pinfunction "P_P$1") (pintype "passive"))
      (node (ref "C10") (pin "1") (pinfunction "1_1") (pintype "passive"))
      (node (ref "C11") (pin "-") (pinfunction "-_-") (pintype "passive"))
      (node (ref "C12") (pin "-") (pinfunction "-_-") (pintype "passive"))
      (node (ref "C13") (pin "-") (pinfunction "-_-") (pintype "passive"))
      (node (ref "C14") (pin "-") (pinfunction "-_-") (pintype "passive"))
      (node (ref "C15") (pin "1") (pinfunction "1_1") (pintype "passive"))
      (node (ref "C16") (pin "2") (pinfunction "2_2") (pintype "passive"))
      (node (ref "C17") (pin "1") (pinfunction "1_1") (pintype "passive"))
      (node (ref "C18") (pin "2") (pinfunction "2_2") (pintype "passive"))
      (node (ref "C19") (pin "1") (pinfunction "1_1") (pintype "passive"))
      (node (ref "C2") (pin "1") (pinfunction "1_1") (pintype "passive"))
      (node (ref "C20") (pin "2") (pinfunction "2_2") (pintype "passive"))
      (node (ref "C21") (pin "2") (pinfunction "2_2") (pintype "passive"))
      (node (ref "C24") (pin "2") (pinfunction "2_2") (pintype "passive"))
      (node (ref "C25") (pin "2") (pinfunction "2_2") (pintype "passive"))
      (node (ref "C26") (pin "1") (pinfunction "1_1") (pintype "passive"))
      (node (ref "C27") (pin "-") (pinfunction "-_-") (pintype "passive"))
      (node (ref "C28") (pin "-") (pinfunction "-_-") (pintype "passive"))
      (node (ref "C29") (pin "1") (pinfunction "1_1") (pintype "passive"))
      (node (ref "C31") (pin "1") (pinfunction "1_1") (pintype "passive"))
      (node (ref "C32") (pin "2") (pinfunction "2_2") (pintype "passive"))
      (node (ref "C33") (pin "1") (pinfunction "1_1") (pintype "passive"))
      (node (ref "C34") (pin "2") (pinfunction "2_2") (pintype "passive"))
      (node (ref "C35") (pin "1") (pinfunction "1_1") (pintype "passive"))
      (node (ref "C4") (pin "-") (pinfunction "-_-") (pintype "passive"))
      (node (ref "C5") (pin "1") (pinfunction "1_1") (pintype "passive"))
      (node (ref "C6") (pin "2") (pinfunction "2_2") (pintype "passive"))
      (node (ref "C8") (pin "-") (pinfunction "-_-") (pintype "passive"))
      (node (ref "C9") (pin "-") (pinfunction "-_-") (pintype "passive"))
      (node (ref "D17") (pin "A") (pinfunction "A_A") (pintype "passive"))
      (node (ref "D2") (pin "A") (pinfunction "A_A") (pintype "passive"))
      (node (ref "D20") (pin "A") (pinfunction "A_A") (pintype "passive"))
      (node (ref "D22") (pin "A") (pinfunction "A_A") (pintype "passive"))
      (node (ref "IC1") (pin "11") (pinfunction "V-_11") (pintype "power_in"))
      (node (ref "IC2") (pin "GND") (pinfunction "GND_GND") (pintype "input"))
      (node (ref "IC3") (pin "19") (pinfunction "VSS_19") (pintype "power_in"))
      (node (ref "IC3") (pin "27") (pinfunction "AVSS_27") (pintype "power_in"))
      (node (ref "IC3") (pin "8") (pinfunction "VSS_8") (pintype "power_in"))
      (node (ref "IC4") (pin "13") (pinfunction "VSS_13") (pintype "power_in"))
      (node (ref "IC4") (pin "2") (pinfunction "COM_2") (pintype "power_in"))
      (node (ref "IC5") (pin "13") (pinfunction "VSS_13") (pintype "power_in"))
      (node (ref "IC5") (pin "2") (pinfunction "COM_2") (pintype "power_in"))
      (node (ref "Q1") (pin "E") (pinfunction "E_E") (pintype "passive"))
      (node (ref "Q14") (pin "S") (pinfunction "S_S") (pintype "passive"))
      (node (ref "Q15") (pin "S") (pinfunction "S_S") (pintype "passive"))
      (node (ref "Q16") (pin "S") (pinfunction "S_S") (pintype "passive"))
      (node (ref "Q17") (pin "S") (pinfunction "S_S") (pintype "passive"))
      (node (ref "Q18") (pin "S") (pinfunction "S_S") (pintype "passive"))
      (node (ref "Q19") (pin "S") (pinfunction "S_S") (pintype "passive"))
      (node (ref "Q5") (pin "E") (pinfunction "E_E") (pintype "passive"))
      (node (ref "Q6") (pin "E") (pinfunction "E_E") (pintype "passive"))
      (node (ref "R11") (pin "4") (pinfunction "2_4") (pintype "passive"))
      (node (ref "R2") (pin "3") (pinfunction "1_3") (pintype "passive"))
      (node (ref "R42") (pin "3") (pinfunction "1_3") (pintype "passive"))
      (node (ref "R45") (pin "4") (pinfunction "2_4") (pintype "passive"))
      (node (ref "R46") (pin "4") (pinfunction "2_4") (pintype "passive"))
      (node (ref "R51") (pin "4") (pinfunction "2_4") (pintype "passive"))
      (node (ref "R52") (pin "4") (pinfunction "2_4") (pintype "passive"))
      (node (ref "R55") (pin "4") (pinfunction "2_4") (pintype "passive"))
      (node (ref "R57") (pin "4") (pinfunction "2_4") (pintype "passive"))
      (node (ref "R9") (pin "3") (pinfunction "1_3") (pintype "passive"))
      (node (ref "X2") (pin "1") (pinfunction "S_1") (pintype "passive"))
      (node (ref "X2") (pin "2") (pinfunction "S_2") (pintype "passive"))
    )
    (net (code "35") (name "Net-(C7-Pad-)") (class "Default")
      (node (ref "C7") (pin "-") (pinfunction "-_-") (pintype "passive"))
      (node (ref "Q5") (pin "C") (pinfunction "C_C") (pintype "passive"))
      (node (ref "SG1") (pin "-") (pinfunction "-_-") (pintype "passive"))
    )
    (net (code "36") (name "Net-(C37-Pad2)") (class "Default")
      (node (ref "C37") (pin "2") (pinfunction "2_2") (pintype "passive"))
      (node (ref "D18") (pin "A") (pinfunction "A_A") (pintype "passive"))
      (node (ref "K1") (pin "1") (pinfunction "1_1") (pintype "passive"))
      (node (ref "Q6") (pin "C") (pinfunction "C_C") (pintype "passive"))
    )
    (net (code "37") (name "Net-(CT_1-P)") (class "Default")
      (node (ref "CT_1") (pin "1") (pinfunction "P_1") (pintype "passive"))
      (node (ref "K1") (pin "C") (pinfunction "P_C") (pintype "passive"))
    )
    (net (code "38") (name "Net-(CT_2-P)") (class "Default")
      (node (ref "C3") (pin "2") (pinfunction "2_2") (pintype "passive"))
      (node (ref "CT_2") (pin "1") (pinfunction "P_1") (pintype "passive"))
      (node (ref "TRF_1") (pin "1") (pinfunction "P1_1") (pintype "passive"))
      (node (ref "TRF_1") (pin "2") (pinfunction "P1_2") (pintype "passive"))
    )
    (net (code "39") (name "Net-(FANB-S)") (class "Default")
      (node (ref "C22") (pin "1") (pinfunction "1_1") (pintype "passive"))
      (node (ref "FAN") (pin "2") (pinfunction "S_2") (pintype "passive"))
      (node (ref "Q1") (pin "C") (pinfunction "C_C") (pintype "passive"))
    )
    (net (code "40") (name "Net-(IC1A-+IN)") (class "Default")
      (node (ref "IC1") (pin "3") (pinfunction "+IN_3") (pintype "input"))
      (node (ref "IC1") (pin "5") (pinfunction "+IN_5") (pintype "input"))
      (node (ref "R17") (pin "3") (pinfunction "1_3") (pintype "passive"))
      (node (ref "R6") (pin "4") (pinfunction "2_4") (pintype "passive"))
    )
    (net (code "41") (name "Net-(IC1A--IN)") (class "Default")
      (node (ref "IC1") (pin "2") (pinfunction "-IN_2") (pintype "input"))
      (node (ref "R12") (pin "3") (pinfunction "1_3") (pintype "passive"))
      (node (ref "R22") (pin "4") (pinfunction "2_4") (pintype "passive"))
    )
    (net (code "42") (name "Net-(IC1A-OUT)") (class "Default")
      (node (ref "IC1") (pin "1") (pinfunction "OUT_1") (pintype "output"))
      (node (ref "R12") (pin "4") (pinfunction "2_4") (pintype "passive"))
      (node (ref "R83") (pin "4") (pinfunction "2_4") (pintype "passive"))
    )
    (net (code "43") (name "Net-(IC1B--IN)") (class "Default")
      (node (ref "IC1") (pin "6") (pinfunction "-IN_6") (pintype "input"))
      (node (ref "R19") (pin "3") (pinfunction "1_3") (pintype "passive"))
      (node (ref "R40") (pin "4") (pinfunction "2_4") (pintype "passive"))
    )
    (net (code "44") (name "Net-(IC1B-OUT)") (class "Default")
      (node (ref "IC1") (pin "7") (pinfunction "OUT_7") (pintype "output"))
      (node (ref "R19") (pin "4") (pinfunction "2_4") (pintype "passive"))
      (node (ref "R77") (pin "4") (pinfunction "2_4") (pintype "passive"))
    )
    (net (code "45") (name "Net-(IC1C-+IN)") (class "Default")
      (node (ref "IC1") (pin "10") (pinfunction "+IN_10") (pintype "input"))
      (node (ref "R11") (pin "3") (pinfunction "1_3") (pintype "passive"))
      (node (ref "R7") (pin "4") (pinfunction "2_4") (pintype "passive"))
    )
    (net (code "46") (name "Net-(IC1D--IN)") (class "Default")
      (node (ref "C25") (pin "1") (pinfunction "1_1") (pintype "passive"))
      (node (ref "IC1") (pin "13") (pinfunction "-IN_13") (pintype "input"))
      (node (ref "R52") (pin "3") (pinfunction "1_3") (pintype "passive"))
      (node (ref "R53") (pin "3") (pinfunction "1_3") (pintype "passive"))
    )
    (net (code "47") (name "Net-(IC3-OSC1{slash}CLKI)") (class "Default")
      (node (ref "C20") (pin "1") (pinfunction "1_1") (pintype "passive"))
      (node (ref "IC3") (pin "9") (pinfunction "OSC1/CLKI_9") (pintype "input"))
      (node (ref "Q7") (pin "2") (pinfunction "2_2") (pintype "passive"))
    )
    (net (code "48") (name "Net-(IC3-RC15{slash}OSC2{slash}CLKO)") (class "Default")
      (node (ref "C21") (pin "1") (pinfunction "1_1") (pintype "passive"))
      (node (ref "IC3") (pin "10") (pinfunction "RC15/OSC2/CLKO_10") (pintype "bidirectional"))
      (node (ref "Q7") (pin "1") (pinfunction "1_1") (pintype "passive"))
    )
    (net (code "49") (name "Net-(IC4-VDD)") (class "Default")
      (node (ref "C31") (pin "2") (pinfunction "2_2") (pintype "passive"))
      (node (ref "C32") (pin "1") (pinfunction "1_1") (pintype "passive"))
      (node (ref "C34") (pin "1") (pinfunction "1_1") (pintype "passive"))
      (node (ref "C8") (pin "+") (pinfunction "+_+") (pintype "passive"))
      (node (ref "D22") (pin "C") (pinfunction "C_C") (pintype "passive"))
      (node (ref "IC4") (pin "9") (pinfunction "VDD_9") (pintype "power_in"))
      (node (ref "IC5") (pin "9") (pinfunction "VDD_9") (pintype "power_in"))
      (node (ref "R10") (pin "3") (pinfunction "1_3") (pintype "passive"))
    )
    (net (code "50") (name "Net-(K1B-O)") (class "Default")
      (node (ref "C30") (pin "1") (pinfunction "1_1") (pintype "passive"))
      (node (ref "K1") (pin "NC") (pinfunction "O_NC") (pintype "passive"))
      (node (ref "R20") (pin "3") (pinfunction "1_3") (pintype "passive"))
      (node (ref "R8") (pin "2") (pinfunction "2_2") (pintype "passive"))
    )
    (net (code "51") (name "Net-(K1B-S)") (class "Default")
      (node (ref "K1") (pin "NO") (pinfunction "S_NO") (pintype "passive"))
      (node (ref "R44") (pin "4") (pinfunction "2_4") (pintype "passive"))
    )
    (net (code "52") (name "Net-(R1-2)") (class "Default")
      (node (ref "R1") (pin "4") (pinfunction "2_4") (pintype "passive"))
      (node (ref "X2") (pin "6") (pinfunction "S_6") (pintype "passive"))
    )
    (net (code "53") (name "Net-(R3-2)") (class "Default")
      (node (ref "R3") (pin "4") (pinfunction "2_4") (pintype "passive"))
      (node (ref "X2") (pin "7") (pinfunction "S_7") (pintype "passive"))
    )
    (net (code "54") (name "Net-(R4-1)") (class "Default")
      (node (ref "C3") (pin "1") (pinfunction "1_1") (pintype "passive"))
      (node (ref "C30") (pin "2") (pinfunction "2_2") (pintype "passive"))
      (node (ref "NEUTRAL") (pin "1") (pinfunction "P1_1") (pintype "passive"))
      (node (ref "NEUTRAL") (pin "2") (pinfunction "P1_2") (pintype "passive"))
      (node (ref "R4") (pin "3") (pinfunction "1_3") (pintype "passive"))
      (node (ref "R8") (pin "1") (pinfunction "1_1") (pintype "passive"))
      (node (ref "TRF_2") (pin "1") (pinfunction "P1_1") (pintype "passive"))
      (node (ref "TRF_2") (pin "2") (pinfunction "P1_2") (pintype "passive"))
    )
    (net (code "55") (name "Net-(R4-2)") (class "Default")
      (node (ref "R4") (pin "4") (pinfunction "2_4") (pintype "passive"))
      (node (ref "R5") (pin "3") (pinfunction "1_3") (pintype "passive"))
    )
    (net (code "56") (name "Net-(R5-2)") (class "Default")
      (node (ref "R5") (pin "4") (pinfunction "2_4") (pintype "passive"))
      (node (ref "R6") (pin "3") (pinfunction "1_3") (pintype "passive"))
    )
    (net (code "57") (name "Net-(R13-2)") (class "Default")
      (node (ref "Q1") (pin "B") (pinfunction "B_B") (pintype "passive"))
      (node (ref "R13") (pin "4") (pinfunction "2_4") (pintype "passive"))
    )
    (net (code "58") (name "Net-(R14-2)") (class "Default")
      (node (ref "Q5") (pin "B") (pinfunction "B_B") (pintype "passive"))
      (node (ref "R14") (pin "4") (pinfunction "2_4") (pintype "passive"))
    )
    (net (code "59") (name "Net-(R20-2)") (class "Default")
      (node (ref "R20") (pin "4") (pinfunction "2_4") (pintype "passive"))
      (node (ref "R21") (pin "3") (pinfunction "1_3") (pintype "passive"))
    )
    (net (code "60") (name "Net-(R21-2)") (class "Default")
      (node (ref "R21") (pin "4") (pinfunction "2_4") (pintype "passive"))
      (node (ref "R22") (pin "3") (pinfunction "1_3") (pintype "passive"))
    )
    (net (code "61") (name "Net-(R23-1)") (class "Default")
      (node (ref "D5") (pin "A") (pinfunction "A_A") (pintype "passive"))
      (node (ref "R23") (pin "3") (pinfunction "1_3") (pintype "passive"))
      (node (ref "R24") (pin "3") (pinfunction "1_3") (pintype "passive"))
      (node (ref "R25") (pin "3") (pinfunction "1_3") (pintype "passive"))
      (node (ref "R30") (pin "3") (pinfunction "1_3") (pintype "passive"))
      (node (ref "R47") (pin "3") (pinfunction "1_3") (pintype "passive"))
    )
    (net (code "62") (name "Net-(R23-2)") (class "Default")
      (node (ref "Q8") (pin "G") (pinfunction "G_G") (pintype "passive"))
      (node (ref "R23") (pin "4") (pinfunction "2_4") (pintype "passive"))
    )
    (net (code "63") (name "Net-(R24-2)") (class "Default")
      (node (ref "Q9") (pin "G") (pinfunction "G_G") (pintype "passive"))
      (node (ref "R24") (pin "4") (pinfunction "2_4") (pintype "passive"))
    )
    (net (code "64") (name "Net-(R25-2)") (class "Default")
      (node (ref "Q10") (pin "G") (pinfunction "G_G") (pintype "passive"))
      (node (ref "R25") (pin "4") (pinfunction "2_4") (pintype "passive"))
    )
    (net (code "65") (name "Net-(R26-1)") (class "Default")
      (node (ref "D6") (pin "A") (pinfunction "A_A") (pintype "passive"))
      (node (ref "R26") (pin "3") (pinfunction "1_3") (pintype "passive"))
      (node (ref "R27") (pin "3") (pinfunction "1_3") (pintype "passive"))
      (node (ref "R29") (pin "3") (pinfunction "1_3") (pintype "passive"))
      (node (ref "R31") (pin "3") (pinfunction "1_3") (pintype "passive"))
      (node (ref "R48") (pin "3") (pinfunction "1_3") (pintype "passive"))
    )
    (net (code "66") (name "Net-(R26-2)") (class "Default")
      (node (ref "Q11") (pin "G") (pinfunction "G_G") (pintype "passive"))
      (node (ref "R26") (pin "4") (pinfunction "2_4") (pintype "passive"))
    )
    (net (code "67") (name "Net-(R27-2)") (class "Default")
      (node (ref "Q12") (pin "G") (pinfunction "G_G") (pintype "passive"))
      (node (ref "R27") (pin "4") (pinfunction "2_4") (pintype "passive"))
    )
    (net (code "68") (name "Net-(R28-2)") (class "Default")
      (node (ref "Q6") (pin "B") (pinfunction "B_B") (pintype "passive"))
      (node (ref "R28") (pin "4") (pinfunction "2_4") (pintype "passive"))
    )
    (net (code "69") (name "Net-(R29-2)") (class "Default")
      (node (ref "Q13") (pin "G") (pinfunction "G_G") (pintype "passive"))
      (node (ref "R29") (pin "4") (pinfunction "2_4") (pintype "passive"))
    )
    (net (code "70") (name "Net-(R32-1)") (class "Default")
      (node (ref "D7") (pin "A") (pinfunction "A_A") (pintype "passive"))
      (node (ref "R32") (pin "3") (pinfunction "1_3") (pintype "passive"))
      (node (ref "R33") (pin "3") (pinfunction "1_3") (pintype "passive"))
      (node (ref "R34") (pin "3") (pinfunction "1_3") (pintype "passive"))
      (node (ref "R38") (pin "3") (pinfunction "1_3") (pintype "passive"))
      (node (ref "R45") (pin "3") (pinfunction "1_3") (pintype "passive"))
      (node (ref "R49") (pin "4") (pinfunction "2_4") (pintype "passive"))
    )
    (net (code "71") (name "Net-(R32-2)") (class "Default")
      (node (ref "Q14") (pin "G") (pinfunction "G_G") (pintype "passive"))
      (node (ref "R32") (pin "4") (pinfunction "2_4") (pintype "passive"))
    )
    (net (code "72") (name "Net-(R33-2)") (class "Default")
      (node (ref "Q15") (pin "G") (pinfunction "G_G") (pintype "passive"))
      (node (ref "R33") (pin "4") (pinfunction "2_4") (pintype "passive"))
    )
    (net (code "73") (name "Net-(R34-2)") (class "Default")
      (node (ref "Q16") (pin "G") (pinfunction "G_G") (pintype "passive"))
      (node (ref "R34") (pin "4") (pinfunction "2_4") (pintype "passive"))
    )
    (net (code "74") (name "Net-(R35-1)") (class "Default")
      (node (ref "D8") (pin "A") (pinfunction "A_A") (pintype "passive"))
      (node (ref "R35") (pin "3") (pinfunction "1_3") (pintype "passive"))
      (node (ref "R36") (pin "3") (pinfunction "1_3") (pintype "passive"))
      (node (ref "R37") (pin "3") (pinfunction "1_3") (pintype "passive"))
      (node (ref "R39") (pin "3") (pinfunction "1_3") (pintype "passive"))
      (node (ref "R46") (pin "3") (pinfunction "1_3") (pintype "passive"))
      (node (ref "R50") (pin "3") (pinfunction "1_3") (pintype "passive"))
    )
    (net (code "75") (name "Net-(R35-2)") (class "Default")
      (node (ref "Q17") (pin "G") (pinfunction "G_G") (pintype "passive"))
      (node (ref "R35") (pin "4") (pinfunction "2_4") (pintype "passive"))
    )
    (net (code "76") (name "Net-(R36-2)") (class "Default")
      (node (ref "Q18") (pin "G") (pinfunction "G_G") (pintype "passive"))
      (node (ref "R36") (pin "4") (pinfunction "2_4") (pintype "passive"))
    )
    (net (code "77") (name "Net-(R37-2)") (class "Default")
      (node (ref "Q19") (pin "G") (pinfunction "G_G") (pintype "passive"))
      (node (ref "R37") (pin "4") (pinfunction "2_4") (pintype "passive"))
    )
    (net (code "78") (name "Net-(R40-1)") (class "Default")
      (node (ref "R40") (pin "3") (pinfunction "1_3") (pintype "passive"))
      (node (ref "R43") (pin "4") (pinfunction "2_4") (pintype "passive"))
    )
    (net (code "79") (name "Net-(R43-1)") (class "Default")
      (node (ref "R43") (pin "3") (pinfunction "1_3") (pintype "passive"))
      (node (ref "R44") (pin "3") (pinfunction "1_3") (pintype "passive"))
    )
    (net (code "80") (name "Net-(R49-1)") (class "Default")
      (node (ref "D10") (pin "A") (pinfunction "A_A") (pintype "passive"))
      (node (ref "D12") (pin "A") (pinfunction "A_A") (pintype "passive"))
      (node (ref "D14") (pin "A") (pinfunction "A_A") (pintype "passive"))
      (node (ref "R49") (pin "3") (pinfunction "1_3") (pintype "passive"))
    )
    (net (code "81") (name "Net-(R50-2)") (class "Default")
      (node (ref "D11") (pin "A") (pinfunction "A_A") (pintype "passive"))
      (node (ref "D13") (pin "A") (pinfunction "A_A") (pintype "passive"))
      (node (ref "D15") (pin "A") (pinfunction "A_A") (pintype "passive"))
      (node (ref "R50") (pin "4") (pinfunction "2_4") (pintype "passive"))
    )
    (net (code "82") (name "V+") (class "Default")
      (node (ref "C22") (pin "2") (pinfunction "2_2") (pintype "passive"))
      (node (ref "C7") (pin "+") (pinfunction "+_+") (pintype "passive"))
      (node (ref "D9") (pin "A") (pinfunction "A_A") (pintype "passive"))
      (node (ref "FAN") (pin "1") (pinfunction "S_1") (pintype "passive"))
      (node (ref "KK5") (pin "P$2") (pinfunction "P$2_P$2") (pintype "bidirectional"))
      (node (ref "R41") (pin "4") (pinfunction "2_4") (pintype "passive"))
      (node (ref "SG1") (pin "+") (pinfunction "+_+") (pintype "passive"))
    )
    (net (code "83") (name "VCC{slash}2") (class "Default")
      (node (ref "C15") (pin "2") (pinfunction "2_2") (pintype "passive"))
      (node (ref "C23") (pin "2") (pinfunction "2_2") (pintype "passive"))
      (node (ref "C6") (pin "1") (pinfunction "1_1") (pintype "passive"))
      (node (ref "IC1") (pin "8") (pinfunction "OUT_8") (pintype "output"))
      (node (ref "IC1") (pin "9") (pinfunction "-IN_9") (pintype "input"))
      (node (ref "R16") (pin "4") (pinfunction "2_4") (pintype "passive"))
      (node (ref "R17") (pin "4") (pinfunction "2_4") (pintype "passive"))
      (node (ref "T2") (pin "P$1") (pinfunction "1_P$1") (pintype "bidirectional"))
    )
    (net (code "84") (name "unconnected-(IC3-VPP{slash}MCLR-Pad1)") (class "Default")
      (node (ref "IC3") (pin "1") (pinfunction "VPP/MCLR_1") (pintype "input"))
    )
    (net (code "85") (name "unconnected-(Q8-PadD)") (class "Default")
      (node (ref "Q8") (pin "D") (pinfunction "D_D") (pintype "passive"))
    )
    (net (code "86") (name "unconnected-(Q9-PadD)") (class "Default")
      (node (ref "Q9") (pin "D") (pinfunction "D_D") (pintype "passive"))
    )
    (net (code "87") (name "unconnected-(Q10-PadD)") (class "Default")
      (node (ref "Q10") (pin "D") (pinfunction "D_D") (pintype "passive"))
    )
    (net (code "88") (name "unconnected-(Q11-PadD)") (class "Default")
      (node (ref "Q11") (pin "D") (pinfunction "D_D") (pintype "passive"))
    )
    (net (code "89") (name "unconnected-(Q12-PadD)") (class "Default")
      (node (ref "Q12") (pin "D") (pinfunction "D_D") (pintype "passive"))
    )
    (net (code "90") (name "unconnected-(Q13-PadD)") (class "Default")
      (node (ref "Q13") (pin "D") (pinfunction "D_D") (pintype "passive"))
    )
    (net (code "91") (name "unconnected-(Q14-PadD)") (class "Default")
      (node (ref "Q14") (pin "D") (pinfunction "D_D") (pintype "passive"))
    )
    (net (code "92") (name "unconnected-(Q15-PadD)") (class "Default")
      (node (ref "Q15") (pin "D") (pinfunction "D_D") (pintype "passive"))
    )
    (net (code "93") (name "unconnected-(Q16-PadD)") (class "Default")
      (node (ref "Q16") (pin "D") (pinfunction "D_D") (pintype "passive"))
    )
    (net (code "94") (name "unconnected-(Q17-PadD)") (class "Default")
      (node (ref "Q17") (pin "D") (pinfunction "D_D") (pintype "passive"))
    )
    (net (code "95") (name "unconnected-(Q18-PadD)") (class "Default")
      (node (ref "Q18") (pin "D") (pinfunction "D_D") (pintype "passive"))
    )
    (net (code "96") (name "unconnected-(Q19-PadD)") (class "Default")
      (node (ref "Q19") (pin "D") (pinfunction "D_D") (pintype "passive"))
    )
    (net (code "97") (name "unconnected-(U$1-K-PadP$1)") (class "Default")
      (node (ref "U$1") (pin "P$1") (pinfunction "K_P$1") (pintype "passive"))
    )
    (net (code "98") (name "unconnected-(U$2-K-PadP$2)") (class "Default")
      (node (ref "U$2") (pin "P$2") (pinfunction "K_P$2") (pintype "passive"))
    )
  )
)
